# CANduino-bootloader.net
KiCad netlist of a schematic drawn in Altium Designer
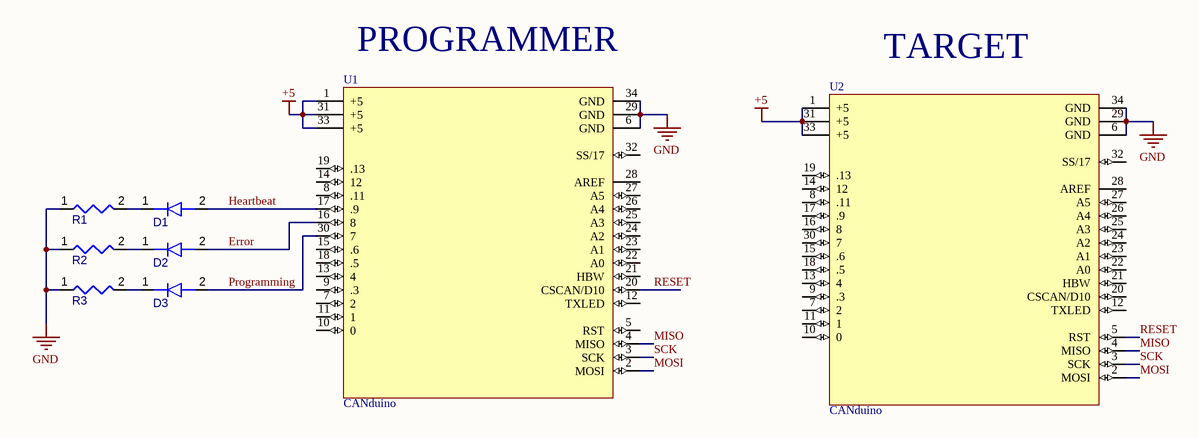
[diagram p0: CANduino-bootloader.SchDoc]

(export (version "E")
  (design (tool "Eeschema 10.0.6"))
  (components
    (comp (ref "D1")
      (value "Diodes")
      (description "Diode")
      (libsource (lib "Selim Mucharski") (part "DIODE-2"))
    )
    (comp (ref "D2")
      (value "Diodes")
      (description "Diode")
      (libsource (lib "Selim Mucharski") (part "DIODE-2"))
    )
    (comp (ref "D3")
      (value "Diodes")
      (description "Diode")
      (libsource (lib "Selim Mucharski") (part "DIODE-2"))
    )
    (comp (ref "R1")
      (value "Resistors")
      (description "Resistor")
      (libsource (lib "Selim Mucharski") (part "RES-2"))
    )
    (comp (ref "R2")
      (value "Resistors")
      (description "Resistor")
      (libsource (lib "Selim Mucharski") (part "RES-2"))
    )
    (comp (ref "R3")
      (value "Resistors")
      (description "Resistor")
      (libsource (lib "Selim Mucharski") (part "RES-2"))
    )
    (comp (ref "U1")
      (value "CANduino")
      (footprint "299-017-299198-1EDAC")
      (libsource (lib "CANduino") (part "CANduino"))
    )
    (comp (ref "U2")
      (value "CANduino")
      (footprint "299-017-299198-1EDAC")
      (libsource (lib "CANduino") (part "CANduino"))
    )
  )
  (nets
    (net (code "1") (name "+5") (class "Default")
      (node (ref "U1") (pin "1") (pinfunction "+5_1") (pintype "passive"))
      (node (ref "U1") (pin "31") (pinfunction "+5_31") (pintype "power_in"))
      (node (ref "U1") (pin "33") (pinfunction "+5_33") (pintype "power_in"))
      (node (ref "U2") (pin "1") (pinfunction "+5_1") (pintype "passive"))
      (node (ref "U2") (pin "31") (pinfunction "+5_31") (pintype "power_in"))
      (node (ref "U2") (pin "33") (pinfunction "+5_33") (pintype "power_in"))
    )
    (net (code "2") (name "/Error") (class "Default")
      (node (ref "D2") (pin "2") (pinfunction "A_2") (pintype "passive"))
      (node (ref "U1") (pin "16") (pinfunction "8_16") (pintype "bidirectional"))
    )
    (net (code "3") (name "/Heartbeat") (class "Default")
      (node (ref "D1") (pin "2") (pinfunction "A_2") (pintype "passive"))
      (node (ref "U1") (pin "17") (pinfunction ".9_17") (pintype "bidirectional"))
    )
    (net (code "4") (name "/MISO") (class "Default")
      (node (ref "U1") (pin "4") (pinfunction "MISO_4") (pintype "bidirectional"))
      (node (ref "U2") (pin "4") (pinfunction "MISO_4") (pintype "bidirectional"))
    )
    (net (code "5") (name "/MOSI") (class "Default")
      (node (ref "U1") (pin "2") (pinfunction "MOSI_2") (pintype "bidirectional"))
      (node (ref "U2") (pin "2") (pinfunction "MOSI_2") (pintype "bidirectional"))
    )
    (net (code "6") (name "/Programming") (class "Default")
      (node (ref "D3") (pin "2") (pinfunction "A_2") (pintype "passive"))
      (node (ref "U1") (pin "30") (pinfunction "7_30") (pintype "bidirectional"))
    )
    (net (code "7") (name "/RESET") (class "Default")
      (node (ref "U1") (pin "20") (pinfunction "CSCAN/D10_20") (pintype "bidirectional"))
      (node (ref "U2") (pin "5") (pinfunction "RST_5") (pintype "bidirectional"))
    )
    (net (code "8") (name "/SCK") (class "Default")
      (node (ref "U1") (pin "3") (pinfunction "SCK_3") (pintype "bidirectional"))
      (node (ref "U2") (pin "3") (pinfunction "SCK_3") (pintype "bidirectional"))
    )
    (net (code "9") (name "GND") (class "Default")
      (node (ref "R1") (pin "1") (pinfunction "1_1") (pintype "passive"))
      (node (ref "R2") (pin "1") (pinfunction "1_1") (pintype "passive"))
      (node (ref "R3") (pin "1") (pinfunction "1_1") (pintype "passive"))
      (node (ref "U1") (pin "29") (pinfunction "GND_29") (pintype "passive"))
      (node (ref "U1") (pin "34") (pinfunction "GND_34") (pintype "passive"))
      (node (ref "U1") (pin "6") (pinfunction "GND_6") (pintype "passive"))
      (node (ref "U2") (pin "29") (pinfunction "GND_29") (pintype "passive"))
      (node (ref "U2") (pin "34") (pinfunction "GND_34") (pintype "passive"))
      (node (ref "U2") (pin "6") (pinfunction "GND_6") (pintype "passive"))
    )
    (net (code "10") (name "Net-(D1-K)") (class "Default")
      (node (ref "D1") (pin "1") (pinfunction "K_1") (pintype "passive"))
      (node (ref "R1") (pin "2") (pinfunction "2_2") (pintype "passive"))
    )
    (net (code "11") (name "Net-(D2-K)") (class "Default")
      (node (ref "D2") (pin "1") (pinfunction "K_1") (pintype "passive"))
      (node (ref "R2") (pin "2") (pinfunction "2_2") (pintype "passive"))
    )
    (net (code "12") (name "Net-(D3-K)") (class "Default")
      (node (ref "D3") (pin "1") (pinfunction "K_1") (pintype "passive"))
      (node (ref "R3") (pin "2") (pinfunction "2_2") (pintype "passive"))
    )
    (net (code "13") (name "unconnected-(U1-.3-Pad9)") (class "Default")
      (node (ref "U1") (pin "9") (pinfunction ".3_9") (pintype "bidirectional"))
    )
    (net (code "14") (name "unconnected-(U1-.5-Pad18)") (class "Default")
      (node (ref "U1") (pin "18") (pinfunction ".5_18") (pintype "bidirectional"))
    )
    (net (code "15") (name "unconnected-(U1-.6-Pad15)") (class "Default")
      (node (ref "U1") (pin "15") (pinfunction ".6_15") (pintype "bidirectional"))
    )
    (net (code "16") (name "unconnected-(U1-.11-Pad8)") (class "Default")
      (node (ref "U1") (pin "8") (pinfunction ".11_8") (pintype "bidirectional"))
    )
    (net (code "17") (name "unconnected-(U1-.13-Pad19)") (class "Default")
      (node (ref "U1") (pin "19") (pinfunction ".13_19") (pintype "bidirectional"))
    )
    (net (code "18") (name "unconnected-(U1-0-Pad10)") (class "Default")
      (node (ref "U1") (pin "10") (pinfunction "0_10") (pintype "bidirectional"))
    )
    (net (code "19") (name "unconnected-(U1-1-Pad11)") (class "Default")
      (node (ref "U1") (pin "11") (pinfunction "1_11") (pintype "bidirectional"))
    )
    (net (code "20") (name "unconnected-(U1-2-Pad7)") (class "Default")
      (node (ref "U1") (pin "7") (pinfunction "2_7") (pintype "bidirectional"))
    )
    (net (code "21") (name "unconnected-(U1-4-Pad13)") (class "Default")
      (node (ref "U1") (pin "13") (pinfunction "4_13") (pintype "bidirectional"))
    )
    (net (code "22") (name "unconnected-(U1-12-Pad14)") (class "Default")
      (node (ref "U1") (pin "14") (pinfunction "12_14") (pintype "bidirectional"))
    )
    (net (code "23") (name "unconnected-(U1-A0-Pad22)") (class "Default")
      (node (ref "U1") (pin "22") (pinfunction "A0_22") (pintype "bidirectional"))
    )
    (net (code "24") (name "unconnected-(U1-A1-Pad23)") (class "Default")
      (node (ref "U1") (pin "23") (pinfunction "A1_23") (pintype "bidirectional"))
    )
    (net (code "25") (name "unconnected-(U1-A2-Pad24)") (class "Default")
      (node (ref "U1") (pin "24") (pinfunction "A2_24") (pintype "bidirectional"))
    )
    (net (code "26") (name "unconnected-(U1-A3-Pad25)") (class "Default")
      (node (ref "U1") (pin "25") (pinfunction "A3_25") (pintype "bidirectional"))
    )
    (net (code "27") (name "unconnected-(U1-A4-Pad26)") (class "Default")
      (node (ref "U1") (pin "26") (pinfunction "A4_26") (pintype "bidirectional"))
    )
    (net (code "28") (name "unconnected-(U1-A5-Pad27)") (class "Default")
      (node (ref "U1") (pin "27") (pinfunction "A5_27") (pintype "bidirectional"))
    )
    (net (code "29") (name "unconnected-(U1-AREF-Pad28)") (class "Default")
      (node (ref "U1") (pin "28") (pinfunction "AREF_28") (pintype "passive"))
    )
    (net (code "30") (name "unconnected-(U1-HBW-Pad21)") (class "Default")
      (node (ref "U1") (pin "21") (pinfunction "HBW_21") (pintype "bidirectional"))
    )
    (net (code "31") (name "unconnected-(U1-RST-Pad5)") (class "Default")
      (node (ref "U1") (pin "5") (pinfunction "RST_5") (pintype "bidirectional"))
    )
    (net (code "32") (name "unconnected-(U1-SS{slash}17-Pad32)") (class "Default")
      (node (ref "U1") (pin "32") (pinfunction "SS/17_32") (pintype "bidirectional"))
    )
    (net (code "33") (name "unconnected-(U1-TXLED-Pad12)") (class "Default")
      (node (ref "U1") (pin "12") (pinfunction "TXLED_12") (pintype "bidirectional"))
    )
    (net (code "34") (name "unconnected-(U2-.3-Pad9)") (class "Default")
      (node (ref "U2") (pin "9") (pinfunction ".3_9") (pintype "bidirectional"))
    )
    (net (code "35") (name "unconnected-(U2-.5-Pad18)") (class "Default")
      (node (ref "U2") (pin "18") (pinfunction ".5_18") (pintype "bidirectional"))
    )
    (net (code "36") (name "unconnected-(U2-.6-Pad15)") (class "Default")
      (node (ref "U2") (pin "15") (pinfunction ".6_15") (pintype "bidirectional"))
    )
    (net (code "37") (name "unconnected-(U2-.9-Pad17)") (class "Default")
      (node (ref "U2") (pin "17") (pinfunction ".9_17") (pintype "bidirectional"))
    )
    (net (code "38") (name "unconnected-(U2-.11-Pad8)") (class "Default")
      (node (ref "U2") (pin "8") (pinfunction ".11_8") (pintype "bidirectional"))
    )
    (net (code "39") (name "unconnected-(U2-.13-Pad19)") (class "Default")
      (node (ref "U2") (pin "19") (pinfunction ".13_19") (pintype "bidirectional"))
    )
    (net (code "40") (name "unconnected-(U2-0-Pad10)") (class "Default")
      (node (ref "U2") (pin "10") (pinfunction "0_10") (pintype "bidirectional"))
    )
    (net (code "41") (name "unconnected-(U2-1-Pad11)") (class "Default")
      (node (ref "U2") (pin "11") (pinfunction "1_11") (pintype "bidirectional"))
    )
    (net (code "42") (name "unconnected-(U2-2-Pad7)") (class "Default")
      (node (ref "U2") (pin "7") (pinfunction "2_7") (pintype "bidirectional"))
    )
    (net (code "43") (name "unconnected-(U2-4-Pad13)") (class "Default")
      (node (ref "U2") (pin "13") (pinfunction "4_13") (pintype "bidirectional"))
    )
    (net (code "44") (name "unconnected-(U2-7-Pad30)") (class "Default")
      (node (ref "U2") (pin "30") (pinfunction "7_30") (pintype "bidirectional"))
    )
    (net (code "45") (name "unconnected-(U2-8-Pad16)") (class "Default")
      (node (ref "U2") (pin "16") (pinfunction "8_16") (pintype "bidirectional"))
    )
    (net (code "46") (name "unconnected-(U2-12-Pad14)") (class "Default")
      (node (ref "U2") (pin "14") (pinfunction "12_14") (pintype "bidirectional"))
    )
    (net (code "47") (name "unconnected-(U2-A0-Pad22)") (class "Default")
      (node (ref "U2") (pin "22") (pinfunction "A0_22") (pintype "bidirectional"))
    )
    (net (code "48") (name "unconnected-(U2-A1-Pad23)") (class "Default")
      (node (ref "U2") (pin "23") (pinfunction "A1_23") (pintype "bidirectional"))
    )
    (net (code "49") (name "unconnected-(U2-A2-Pad24)") (class "Default")
      (node (ref "U2") (pin "24") (pinfunction "A2_24") (pintype "bidirectional"))
    )
    (net (code "50") (name "unconnected-(U2-A3-Pad25)") (class "Default")
      (node (ref "U2") (pin "25") (pinfunction "A3_25") (pintype "bidirectional"))
    )
    (net (code "51") (name "unconnected-(U2-A4-Pad26)") (class "Default")
      (node (ref "U2") (pin "26") (pinfunction "A4_26") (pintype "bidirectional"))
    )
    (net (code "52") (name "unconnected-(U2-A5-Pad27)") (class "Default")
      (node (ref "U2") (pin "27") (pinfunction "A5_27") (pintype "bidirectional"))
    )
    (net (code "53") (name "unconnected-(U2-AREF-Pad28)") (class "Default")
      (node (ref "U2") (pin "28") (pinfunction "AREF_28") (pintype "passive"))
    )
    (net (code "54") (name "unconnected-(U2-CSCAN{slash}D10-Pad20)") (class "Default")
      (node (ref "U2") (pin "20") (pinfunction "CSCAN/D10_20") (pintype "bidirectional"))
    )
    (net (code "55") (name "unconnected-(U2-HBW-Pad21)") (class "Default")
      (node (ref "U2") (pin "21") (pinfunction "HBW_21") (pintype "bidirectional"))
    )
    (net (code "56") (name "unconnected-(U2-SS{slash}17-Pad32)") (class "Default")
      (node (ref "U2") (pin "32") (pinfunction "SS/17_32") (pintype "bidirectional"))
    )
    (net (code "57") (name "unconnected-(U2-TXLED-Pad12)") (class "Default")
      (node (ref "U2") (pin "12") (pinfunction "TXLED_12") (pintype "bidirectional"))
    )
  )
)
